# fm.net
KiCad netlist of a schematic drawn in EAGLE
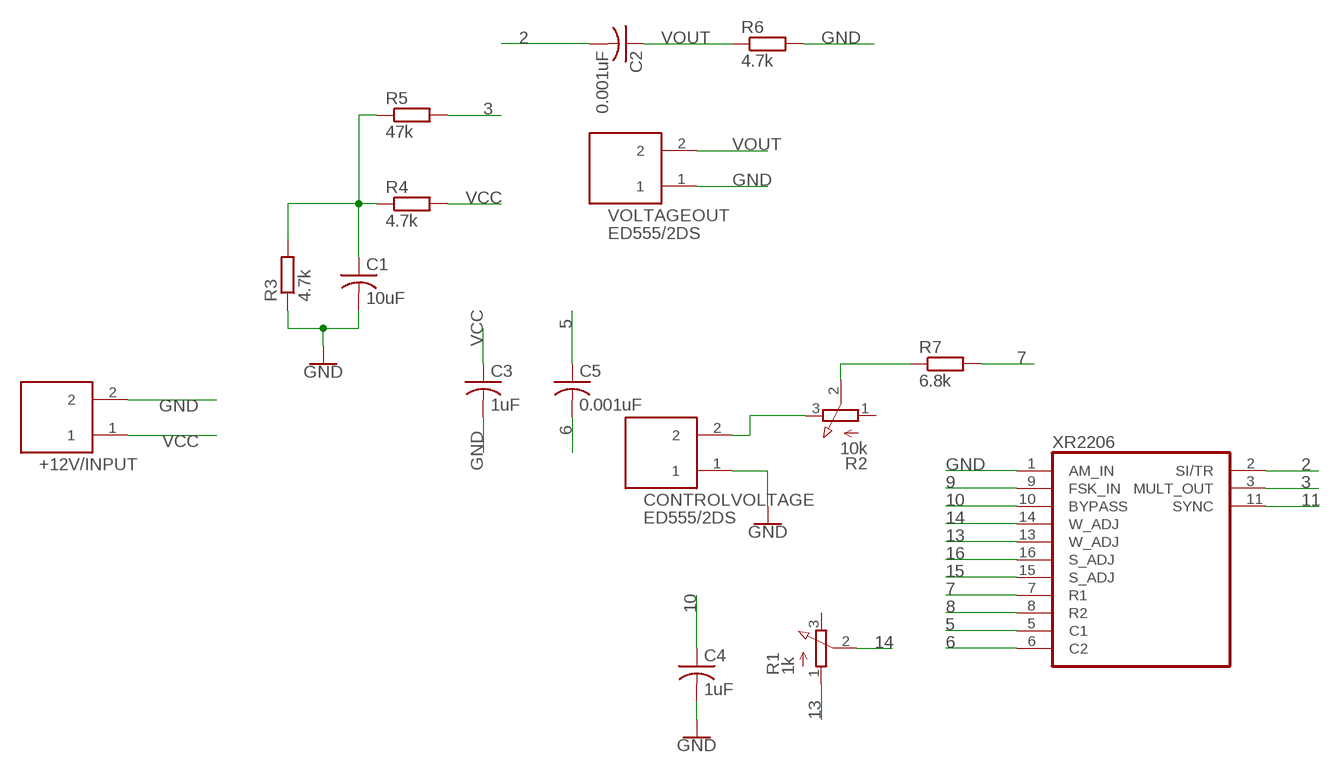
[diagram p0: schematic, sheet 1]

(export (version "E")
  (design (tool "Eeschema 10.0.6"))
  (components
    (comp (ref "+12V/INPUT")
      (value "ED555/2DS")
      (footprint "eagle-import:ED555_2DS")
      (libsource (lib "eagle-import") (part "ED555/2DS"))
    )
    (comp (ref "C1")
      (value "10uF")
      (footprint "eagle-import:C050-030X075")
      (libsource (lib "eagle-import") (part "C-US050-030X075"))
    )
    (comp (ref "C2")
      (value "0.001uF")
      (footprint "eagle-import:C050-030X075")
      (libsource (lib "eagle-import") (part "C-US050-030X075"))
    )
    (comp (ref "C3")
      (value "1uF")
      (footprint "eagle-import:C050-030X075")
      (libsource (lib "eagle-import") (part "C-US050-030X075"))
    )
    (comp (ref "C4")
      (value "1uF")
      (footprint "eagle-import:C050-030X075")
      (libsource (lib "eagle-import") (part "C-US050-030X075"))
    )
    (comp (ref "C5")
      (value "0.001uF")
      (footprint "eagle-import:C050-030X075")
      (libsource (lib "eagle-import") (part "C-US050-030X075"))
    )
    (comp (ref "CONTROLVOLTAGE")
      (value "ED555/2DS")
      (footprint "eagle-import:ED555_2DS")
      (libsource (lib "eagle-import") (part "ED555/2DS"))
    )
    (comp (ref "R1")
      (value "1k")
      (footprint "eagle-import:3RP_1610N")
      (libsource (lib "eagle-import") (part "3RP/1610N"))
    )
    (comp (ref "R2")
      (value "10k")
      (footprint "eagle-import:3RP_1610N")
      (libsource (lib "eagle-import") (part "3RP/1610N"))
    )
    (comp (ref "R3")
      (value "4.7k")
      (footprint "eagle-import:0207_10")
      (libsource (lib "eagle-import") (part "R-EU_0207/10"))
    )
    (comp (ref "R4")
      (value "4.7k")
      (footprint "eagle-import:0207_10")
      (libsource (lib "eagle-import") (part "R-EU_0207/10"))
    )
    (comp (ref "R5")
      (value "47k")
      (footprint "eagle-import:0207_10")
      (libsource (lib "eagle-import") (part "R-EU_0207/10"))
    )
    (comp (ref "R6")
      (value "4.7k")
      (footprint "eagle-import:0207_10")
      (libsource (lib "eagle-import") (part "R-EU_0207/10"))
    )
    (comp (ref "R7")
      (value "6.8k")
      (footprint "eagle-import:0207_10")
      (libsource (lib "eagle-import") (part "R-EU_0207/10"))
    )
    (comp (ref "VOLTAGEOUT")
      (value "ED555/2DS")
      (footprint "eagle-import:ED555_2DS")
      (libsource (lib "eagle-import") (part "ED555/2DS"))
    )
    (comp (ref "XR2206")
      (value "XR-2206")
      (footprint "eagle-import:DIL16")
      (libsource (lib "eagle-import") (part "XR-2206"))
    )
  )
  (nets
    (net (code "1") (name "/2") (class "Default")
      (node (ref "C2") (pin "2") (pinfunction "2_2") (pintype "passive"))
      (node (ref "XR2206") (pin "2") (pinfunction "SI/TR_2") (pintype "output"))
    )
    (net (code "2") (name "/3") (class "Default")
      (node (ref "R5") (pin "2") (pinfunction "2_2") (pintype "passive"))
      (node (ref "XR2206") (pin "3") (pinfunction "MULT_OUT_3") (pintype "output"))
    )
    (net (code "3") (name "/5") (class "Default")
      (node (ref "C5") (pin "1") (pinfunction "1_1") (pintype "passive"))
      (node (ref "XR2206") (pin "5") (pinfunction "C1_5") (pintype "input"))
    )
    (net (code "4") (name "/6") (class "Default")
      (node (ref "C5") (pin "2") (pinfunction "2_2") (pintype "passive"))
      (node (ref "XR2206") (pin "6") (pinfunction "C2_6") (pintype "input"))
    )
    (net (code "5") (name "/7") (class "Default")
      (node (ref "R7") (pin "2") (pinfunction "2_2") (pintype "passive"))
      (node (ref "XR2206") (pin "7") (pinfunction "R1_7") (pintype "input"))
    )
    (net (code "6") (name "/8") (class "Default")
      (node (ref "XR2206") (pin "8") (pinfunction "R2_8") (pintype "input"))
    )
    (net (code "7") (name "/9") (class "Default")
      (node (ref "XR2206") (pin "9") (pinfunction "FSK_IN_9") (pintype "input"))
    )
    (net (code "8") (name "/10") (class "Default")
      (node (ref "C4") (pin "1") (pinfunction "1_1") (pintype "passive"))
      (node (ref "XR2206") (pin "10") (pinfunction "BYPASS_10") (pintype "input"))
    )
    (net (code "9") (name "/11") (class "Default")
      (node (ref "XR2206") (pin "11") (pinfunction "SYNC_11") (pintype "output"))
    )
    (net (code "10") (name "/13") (class "Default")
      (node (ref "R1") (pin "1") (pinfunction "A_1") (pintype "passive"))
      (node (ref "XR2206") (pin "13") (pinfunction "W_ADJ_13") (pintype "input"))
    )
    (net (code "11") (name "/14") (class "Default")
      (node (ref "R1") (pin "2") (pinfunction "S_2") (pintype "passive"))
      (node (ref "XR2206") (pin "14") (pinfunction "W_ADJ_14") (pintype "input"))
    )
    (net (code "12") (name "/15") (class "Default")
      (node (ref "XR2206") (pin "15") (pinfunction "S_ADJ_15") (pintype "input"))
    )
    (net (code "13") (name "/16") (class "Default")
      (node (ref "XR2206") (pin "16") (pinfunction "S_ADJ_16") (pintype "input"))
    )
    (net (code "14") (name "/VCC") (class "Default")
      (node (ref "+12V/INPUT") (pin "1") (pinfunction "1_1") (pintype "bidirectional"))
      (node (ref "C3") (pin "1") (pinfunction "1_1") (pintype "passive"))
      (node (ref "R4") (pin "2") (pinfunction "2_2") (pintype "passive"))
    )
    (net (code "15") (name "/VOUT") (class "Default")
      (node (ref "C2") (pin "1") (pinfunction "1_1") (pintype "passive"))
      (node (ref "R6") (pin "1") (pinfunction "1_1") (pintype "passive"))
      (node (ref "VOLTAGEOUT") (pin "2") (pinfunction "2_2") (pintype "bidirectional"))
    )
    (net (code "16") (name "GND") (class "Default")
      (node (ref "+12V/INPUT") (pin "2") (pinfunction "2_2") (pintype "bidirectional"))
      (node (ref "C1") (pin "2") (pinfunction "2_2") (pintype "passive"))
      (node (ref "C3") (pin "2") (pinfunction "2_2") (pintype "passive"))
      (node (ref "C4") (pin "2") (pinfunction "2_2") (pintype "passive"))
      (node (ref "CONTROLVOLTAGE") (pin "1") (pinfunction "1_1") (pintype "bidirectional"))
      (node (ref "R3") (pin "1") (pinfunction "1_1") (pintype "passive"))
      (node (ref "R6") (pin "2") (pinfunction "2_2") (pintype "passive"))
      (node (ref "VOLTAGEOUT") (pin "1") (pinfunction "1_1") (pintype "bidirectional"))
      (node (ref "XR2206") (pin "1") (pinfunction "AM_IN_1") (pintype "input"))
    )
    (net (code "17") (name "Net-(C1-Pad1)") (class "Default")
      (node (ref "C1") (pin "1") (pinfunction "1_1") (pintype "passive"))
      (node (ref "R3") (pin "2") (pinfunction "2_2") (pintype "passive"))
      (node (ref "R4") (pin "1") (pinfunction "1_1") (pintype "passive"))
      (node (ref "R5") (pin "1") (pinfunction "1_1") (pintype "passive"))
    )
    (net (code "18") (name "Net-(R2-E)") (class "Default")
      (node (ref "CONTROLVOLTAGE") (pin "2") (pinfunction "2_2") (pintype "bidirectional"))
      (node (ref "R2") (pin "3") (pinfunction "E_3") (pintype "passive"))
    )
    (net (code "19") (name "Net-(R2-S)") (class "Default")
      (node (ref "R2") (pin "2") (pinfunction "S_2") (pintype "passive"))
      (node (ref "R7") (pin "1") (pinfunction "1_1") (pintype "passive"))
    )
    (net (code "20") (name "unconnected-(R1-E-Pad3)") (class "Default")
      (node (ref "R1") (pin "3") (pinfunction "E_3") (pintype "passive"))
    )
    (net (code "21") (name "unconnected-(R2-A-Pad1)") (class "Default")
      (node (ref "R2") (pin "1") (pinfunction "A_1") (pintype "passive"))
    )
  )
)
